# transmiter_switch.net
KiCad netlist of a schematic drawn in EAGLE
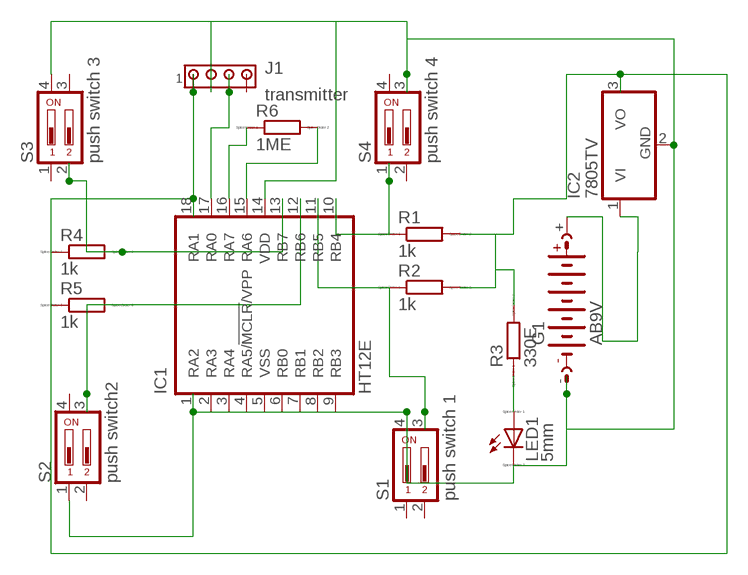
[diagram p0: schematic, sheet 1]

(export (version "E")
  (design (tool "Eeschema 10.0.6"))
  (components
    (comp (ref "G1")
      (value "AB9V")
      (footprint "eagle-import:AB9V")
      (libsource (lib "eagle-import") (part "AB9V"))
    )
    (comp (ref "IC1")
      (value "HT12E")
      (footprint "eagle-import:DIL18")
      (libsource (lib "eagle-import") (part "PIC16F1826/27P"))
    )
    (comp (ref "IC2")
      (value "7805TV")
      (footprint "eagle-import:TO220V")
      (libsource (lib "eagle-import") (part "78TV05"))
    )
    (comp (ref "J1")
      (value "transmitter")
      (footprint "eagle-import:10X04MTA")
      (libsource (lib "eagle-import") (part "MTA04-100"))
    )
    (comp (ref "LED1")
      (value "5mm")
      (footprint "eagle-import:LED_LD260")
      (libsource (lib "eagle-import") (part "LED_ELD260"))
    )
    (comp (ref "R1")
      (value "1k")
      (footprint "eagle-import:0204_7")
      (libsource (lib "eagle-import") (part "R0204/7"))
    )
    (comp (ref "R2")
      (value "1k")
      (footprint "eagle-import:0204_7")
      (libsource (lib "eagle-import") (part "R0204/7"))
    )
    (comp (ref "R3")
      (value "330E")
      (footprint "eagle-import:0204_7")
      (libsource (lib "eagle-import") (part "R0204/7"))
    )
    (comp (ref "R4")
      (value "1k")
      (footprint "eagle-import:0204_7")
      (libsource (lib "eagle-import") (part "R0204/7"))
    )
    (comp (ref "R5")
      (value "1k")
      (footprint "eagle-import:0204_7")
      (libsource (lib "eagle-import") (part "R0204/7"))
    )
    (comp (ref "R6")
      (value "1ME")
      (footprint "eagle-import:0204_7")
      (libsource (lib "eagle-import") (part "R0204/7"))
    )
    (comp (ref "S1")
      (value "push switch 1")
      (footprint "eagle-import:DS-02")
      (libsource (lib "eagle-import") (part "DS02"))
    )
    (comp (ref "S2")
      (value "push switch2")
      (footprint "eagle-import:DS-02")
      (libsource (lib "eagle-import") (part "DS02"))
    )
    (comp (ref "S3")
      (value "push switch 3")
      (footprint "eagle-import:DS-02")
      (libsource (lib "eagle-import") (part "DS02"))
    )
    (comp (ref "S4")
      (value "push switch 4")
      (footprint "eagle-import:DS-02")
      (libsource (lib "eagle-import") (part "DS02"))
    )
  )
  (nets
    (net (code "1") (name "Net-(IC1-RA0)") (class "Default")
      (node (ref "IC1") (pin "17") (pinfunction "RA0_17") (pintype "bidirectional"))
      (node (ref "J1") (pin "3") (pinfunction "3_3") (pintype "passive"))
    )
    (net (code "2") (name "Net-(IC1-RA1)") (class "Default")
      (node (ref "IC1") (pin "18") (pinfunction "RA1_18") (pintype "bidirectional"))
      (node (ref "IC2") (pin "3") (pinfunction "VO_3") (pintype "passive"))
      (node (ref "J1") (pin "1") (pinfunction "1_1") (pintype "passive"))
      (node (ref "R1") (pin "2") (pinfunction "2_2") (pintype "passive"))
      (node (ref "R2") (pin "2") (pinfunction "2_2") (pintype "passive"))
      (node (ref "R3") (pin "2") (pinfunction "2_2") (pintype "passive"))
      (node (ref "R4") (pin "1") (pinfunction "1_1") (pintype "passive"))
      (node (ref "R5") (pin "1") (pinfunction "1_1") (pintype "passive"))
    )
    (net (code "3") (name "Net-(IC1-RA2)") (class "Default")
      (node (ref "G1") (pin "-") (pinfunction "-_-") (pintype "passive"))
      (node (ref "IC1") (pin "1") (pinfunction "RA2_1") (pintype "bidirectional"))
      (node (ref "IC1") (pin "14") (pinfunction "VDD_14") (pintype "power_in"))
      (node (ref "IC1") (pin "2") (pinfunction "RA3_2") (pintype "bidirectional"))
      (node (ref "IC1") (pin "3") (pinfunction "RA4_3") (pintype "bidirectional"))
      (node (ref "IC1") (pin "4") (pinfunction "RA5/~{MCLR}/VPP_4") (pintype "bidirectional"))
      (node (ref "IC1") (pin "5") (pinfunction "VSS_5") (pintype "power_in"))
      (node (ref "IC1") (pin "6") (pinfunction "RB0_6") (pintype "bidirectional"))
      (node (ref "IC1") (pin "7") (pinfunction "RB1_7") (pintype "bidirectional"))
      (node (ref "IC1") (pin "8") (pinfunction "RB2_8") (pintype "bidirectional"))
      (node (ref "IC1") (pin "9") (pinfunction "RB3_9") (pintype "bidirectional"))
      (node (ref "IC2") (pin "2") (pinfunction "GND_2") (pintype "passive"))
      (node (ref "J1") (pin "2") (pinfunction "2_2") (pintype "passive"))
      (node (ref "LED1") (pin "K") (pinfunction "C_K") (pintype "passive"))
      (node (ref "S1") (pin "4") (pinfunction "4_4") (pintype "passive"))
      (node (ref "S2") (pin "1") (pinfunction "1_1") (pintype "passive"))
      (node (ref "S3") (pin "4") (pinfunction "4_4") (pintype "passive"))
      (node (ref "S4") (pin "3") (pinfunction "3_3") (pintype "passive"))
    )
    (net (code "4") (name "Net-(IC1-RA6)") (class "Default")
      (node (ref "IC1") (pin "15") (pinfunction "RA6_15") (pintype "bidirectional"))
      (node (ref "R6") (pin "2") (pinfunction "2_2") (pintype "passive"))
    )
    (net (code "5") (name "Net-(IC1-RA7)") (class "Default")
      (node (ref "IC1") (pin "16") (pinfunction "RA7_16") (pintype "bidirectional"))
      (node (ref "R6") (pin "1") (pinfunction "1_1") (pintype "passive"))
    )
    (net (code "6") (name "Net-(IC1-RB4)") (class "Default")
      (node (ref "IC1") (pin "10") (pinfunction "RB4_10") (pintype "bidirectional"))
      (node (ref "R1") (pin "1") (pinfunction "1_1") (pintype "passive"))
      (node (ref "S4") (pin "1") (pinfunction "1_1") (pintype "passive"))
    )
    (net (code "7") (name "Net-(IC1-RB5)") (class "Default")
      (node (ref "IC1") (pin "11") (pinfunction "RB5_11") (pintype "bidirectional"))
      (node (ref "R2") (pin "1") (pinfunction "1_1") (pintype "passive"))
      (node (ref "S1") (pin "3") (pinfunction "3_3") (pintype "passive"))
    )
    (net (code "8") (name "Net-(IC1-RB6)") (class "Default")
      (node (ref "IC1") (pin "12") (pinfunction "RB6_12") (pintype "bidirectional"))
      (node (ref "R5") (pin "2") (pinfunction "2_2") (pintype "passive"))
      (node (ref "S2") (pin "3") (pinfunction "3_3") (pintype "passive"))
    )
    (net (code "9") (name "Net-(IC1-RB7)") (class "Default")
      (node (ref "IC1") (pin "13") (pinfunction "RB7_13") (pintype "bidirectional"))
      (node (ref "R4") (pin "2") (pinfunction "2_2") (pintype "passive"))
      (node (ref "S3") (pin "2") (pinfunction "2_2") (pintype "passive"))
    )
    (net (code "10") (name "Net-(IC2-VI)") (class "Default")
      (node (ref "G1") (pin "+") (pinfunction "+_+") (pintype "passive"))
      (node (ref "IC2") (pin "1") (pinfunction "VI_1") (pintype "input"))
    )
    (net (code "11") (name "Net-(LED1-PadA)") (class "Default")
      (node (ref "LED1") (pin "A") (pinfunction "A_A") (pintype "passive"))
      (node (ref "R3") (pin "1") (pinfunction "1_1") (pintype "passive"))
    )
    (net (code "12") (name "unconnected-(J1-Pad4)") (class "Default")
      (node (ref "J1") (pin "4") (pinfunction "4_4") (pintype "passive"))
    )
    (net (code "13") (name "unconnected-(S1-Pad1)") (class "Default")
      (node (ref "S1") (pin "1") (pinfunction "1_1") (pintype "passive"))
    )
    (net (code "14") (name "unconnected-(S1-Pad2)") (class "Default")
      (node (ref "S1") (pin "2") (pinfunction "2_2") (pintype "passive"))
    )
    (net (code "15") (name "unconnected-(S2-Pad2)") (class "Default")
      (node (ref "S2") (pin "2") (pinfunction "2_2") (pintype "passive"))
    )
    (net (code "16") (name "unconnected-(S2-Pad4)") (class "Default")
      (node (ref "S2") (pin "4") (pinfunction "4_4") (pintype "passive"))
    )
    (net (code "17") (name "unconnected-(S3-Pad1)") (class "Default")
      (node (ref "S3") (pin "1") (pinfunction "1_1") (pintype "passive"))
    )
    (net (code "18") (name "unconnected-(S3-Pad3)") (class "Default")
      (node (ref "S3") (pin "3") (pinfunction "3_3") (pintype "passive"))
    )
    (net (code "19") (name "unconnected-(S4-Pad2)") (class "Default")
      (node (ref "S4") (pin "2") (pinfunction "2_2") (pintype "passive"))
    )
    (net (code "20") (name "unconnected-(S4-Pad4)") (class "Default")
      (node (ref "S4") (pin "4") (pinfunction "4_4") (pintype "passive"))
    )
  )
)
